# PuzzleBox.net
KiCad netlist of a schematic drawn in EasyEDA
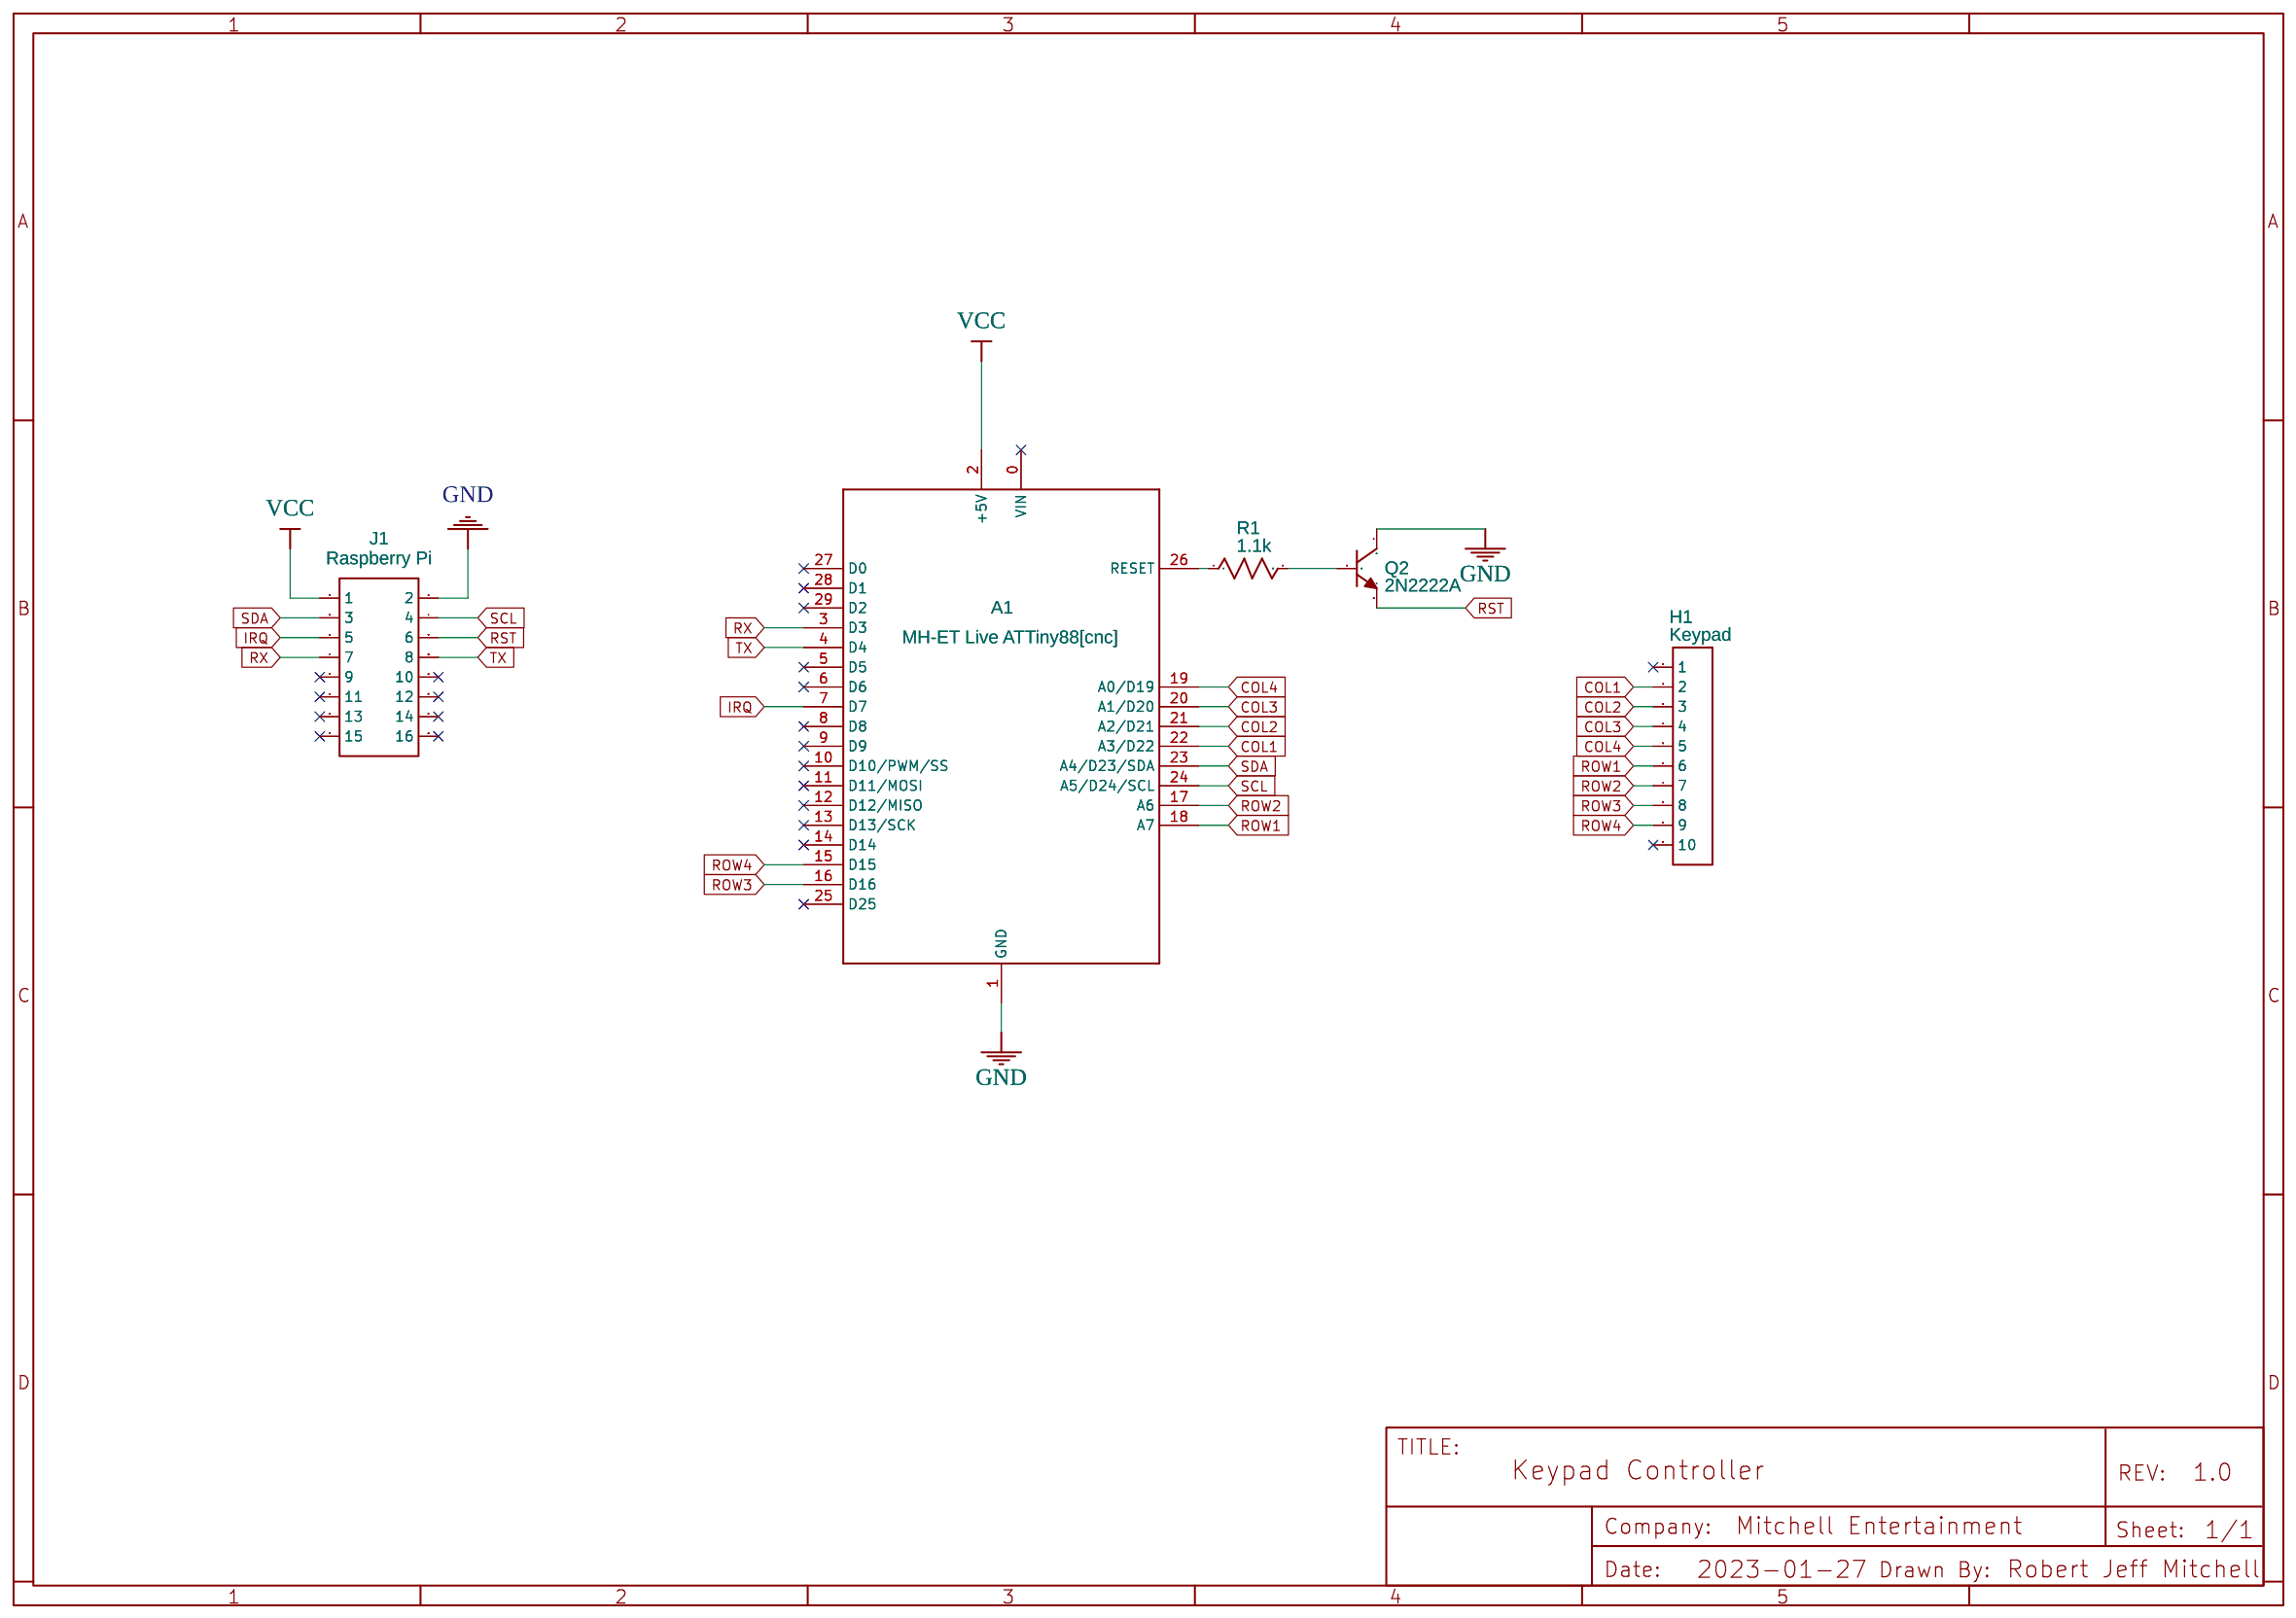
[diagram p0: schematic sheet]

(export (version "E")
  (design (tool "Eeschema 10.0.6"))
  (components
    (comp (ref "A1")
      (value "MH-ET Live ATTiny88[cnc]")
      (libsource (lib "") (part "MH-ET Live ATTiny88[cnc]"))
    )
    (comp (ref "H1")
      (value "Keypad")
      (fields (field (name "BOM_Supplier Part") "C35445"))
      (libsource (lib "") (part "HDR-F-2.54_1x10"))
    )
    (comp (ref "J1")
      (value "Raspberry Pi")
      (fields (field (name "BOM_Supplier Part") "C68234"))
      (libsource (lib "") (part "HDR-M-2.54_2x8"))
    )
    (comp (ref "Q2")
      (value "2N2222A")
      (fields (field (name "BOM_Supplier Part") "C358533"))
      (libsource (lib "") (part "2N2222A"))
    )
    (comp (ref "R1") (value "1.1k") (libsource (lib "") (part "R_AXIAL-0.4_US")))
  )
  (nets
    (net (code "1") (name "COL1") (class "Default")
      (node (ref "A1") (pin "22") (pinfunction "A3/D22_22") (pintype "unspecified"))
      (node (ref "H1") (pin "2") (pinfunction "2_2") (pintype "unspecified"))
    )
    (net (code "2") (name "COL2") (class "Default")
      (node (ref "A1") (pin "21") (pinfunction "A2/D21_21") (pintype "unspecified"))
      (node (ref "H1") (pin "3") (pinfunction "3_3") (pintype "unspecified"))
    )
    (net (code "3") (name "COL3") (class "Default")
      (node (ref "A1") (pin "20") (pinfunction "A1/D20_20") (pintype "unspecified"))
      (node (ref "H1") (pin "4") (pinfunction "4_4") (pintype "unspecified"))
    )
    (net (code "4") (name "COL4") (class "Default")
      (node (ref "A1") (pin "19") (pinfunction "A0/D19_19") (pintype "unspecified"))
      (node (ref "H1") (pin "5") (pinfunction "5_5") (pintype "unspecified"))
    )
    (net (code "5") (name "GND") (class "Default")
      (node (ref "A1") (pin "1") (pinfunction "GND_1") (pintype "passive"))
      (node (ref "J1") (pin "2") (pinfunction "2_2") (pintype "input"))
      (node (ref "Q2") (pin "1") (pinfunction "C_1") (pintype "unspecified"))
    )
    (net (code "6") (name "IRQ") (class "Default")
      (node (ref "A1") (pin "7") (pinfunction "D7_7") (pintype "unspecified"))
      (node (ref "J1") (pin "5") (pinfunction "5_5") (pintype "input"))
    )
    (net (code "7") (name "Net-(A1-RESET)") (class "Default")
      (node (ref "A1") (pin "26") (pinfunction "RESET_26") (pintype "unspecified"))
      (node (ref "R1") (pin "1") (pinfunction "1_1") (pintype "unspecified"))
    )
    (net (code "8") (name "Net-(Q2-B)") (class "Default")
      (node (ref "Q2") (pin "2") (pinfunction "B_2") (pintype "unspecified"))
      (node (ref "R1") (pin "2") (pinfunction "2_2") (pintype "unspecified"))
    )
    (net (code "9") (name "ROW1") (class "Default")
      (node (ref "A1") (pin "18") (pinfunction "A7_18") (pintype "unspecified"))
      (node (ref "H1") (pin "6") (pinfunction "6_6") (pintype "unspecified"))
    )
    (net (code "10") (name "ROW2") (class "Default")
      (node (ref "A1") (pin "17") (pinfunction "A6_17") (pintype "unspecified"))
      (node (ref "H1") (pin "7") (pinfunction "7_7") (pintype "unspecified"))
    )
    (net (code "11") (name "ROW3") (class "Default")
      (node (ref "A1") (pin "16") (pinfunction "D16_16") (pintype "unspecified"))
      (node (ref "H1") (pin "8") (pinfunction "8_8") (pintype "unspecified"))
    )
    (net (code "12") (name "ROW4") (class "Default")
      (node (ref "A1") (pin "15") (pinfunction "D15_15") (pintype "unspecified"))
      (node (ref "H1") (pin "9") (pinfunction "9_9") (pintype "unspecified"))
    )
    (net (code "13") (name "RST") (class "Default")
      (node (ref "J1") (pin "6") (pinfunction "6_6") (pintype "input"))
      (node (ref "Q2") (pin "3") (pinfunction "E_3") (pintype "unspecified"))
    )
    (net (code "14") (name "RX") (class "Default")
      (node (ref "A1") (pin "3") (pinfunction "D3_3") (pintype "unspecified"))
      (node (ref "J1") (pin "7") (pinfunction "7_7") (pintype "input"))
    )
    (net (code "15") (name "SCL") (class "Default")
      (node (ref "A1") (pin "24") (pinfunction "A5/D24/SCL_24") (pintype "unspecified"))
      (node (ref "J1") (pin "4") (pinfunction "4_4") (pintype "input"))
    )
    (net (code "16") (name "SDA") (class "Default")
      (node (ref "A1") (pin "23") (pinfunction "A4/D23/SDA_23") (pintype "unspecified"))
      (node (ref "J1") (pin "3") (pinfunction "3_3") (pintype "input"))
    )
    (net (code "17") (name "TX") (class "Default")
      (node (ref "A1") (pin "4") (pinfunction "D4_4") (pintype "unspecified"))
      (node (ref "J1") (pin "8") (pinfunction "8_8") (pintype "input"))
    )
    (net (code "18") (name "VCC") (class "Default")
      (node (ref "A1") (pin "2") (pinfunction "+5V_2") (pintype "passive"))
      (node (ref "J1") (pin "1") (pinfunction "1_1") (pintype "input"))
    )
    (net (code "19") (name "unconnected-(A1-D0-Pad27)") (class "Default")
      (node (ref "A1") (pin "27") (pinfunction "D0_27") (pintype "unspecified+no_connect"))
    )
    (net (code "20") (name "unconnected-(A1-D1-Pad28)") (class "Default")
      (node (ref "A1") (pin "28") (pinfunction "D1_28") (pintype "unspecified+no_connect"))
    )
    (net (code "21") (name "unconnected-(A1-D2-Pad29)") (class "Default")
      (node (ref "A1") (pin "29") (pinfunction "D2_29") (pintype "unspecified+no_connect"))
    )
    (net (code "22") (name "unconnected-(A1-D5-Pad5)") (class "Default")
      (node (ref "A1") (pin "5") (pinfunction "D5_5") (pintype "unspecified+no_connect"))
    )
    (net (code "23") (name "unconnected-(A1-D6-Pad6)") (class "Default")
      (node (ref "A1") (pin "6") (pinfunction "D6_6") (pintype "unspecified+no_connect"))
    )
    (net (code "24") (name "unconnected-(A1-D8-Pad8)") (class "Default")
      (node (ref "A1") (pin "8") (pinfunction "D8_8") (pintype "unspecified+no_connect"))
    )
    (net (code "25") (name "unconnected-(A1-D9-Pad9)") (class "Default")
      (node (ref "A1") (pin "9") (pinfunction "D9_9") (pintype "unspecified+no_connect"))
    )
    (net (code "26") (name "unconnected-(A1-D10{slash}PWM{slash}SS-Pad10)") (class "Default")
      (node (ref "A1") (pin "10") (pinfunction "D10/PWM/SS_10") (pintype "unspecified+no_connect"))
    )
    (net (code "27") (name "unconnected-(A1-D11{slash}MOSI-Pad11)") (class "Default")
      (node (ref "A1") (pin "11") (pinfunction "D11/MOSI_11") (pintype "unspecified+no_connect"))
    )
    (net (code "28") (name "unconnected-(A1-D12{slash}MISO-Pad12)") (class "Default")
      (node (ref "A1") (pin "12") (pinfunction "D12/MISO_12") (pintype "unspecified+no_connect"))
    )
    (net (code "29") (name "unconnected-(A1-D13{slash}SCK-Pad13)") (class "Default")
      (node (ref "A1") (pin "13") (pinfunction "D13/SCK_13") (pintype "unspecified+no_connect"))
    )
    (net (code "30") (name "unconnected-(A1-D14-Pad14)") (class "Default")
      (node (ref "A1") (pin "14") (pinfunction "D14_14") (pintype "unspecified+no_connect"))
    )
    (net (code "31") (name "unconnected-(A1-D25-Pad25)") (class "Default")
      (node (ref "A1") (pin "25") (pinfunction "D25_25") (pintype "unspecified+no_connect"))
    )
    (net (code "32") (name "unconnected-(A1-VIN-Pad0)") (class "Default")
      (node (ref "A1") (pin "0") (pinfunction "VIN_0") (pintype "passive+no_connect"))
    )
    (net (code "33") (name "unconnected-(H1-Pad1)") (class "Default")
      (node (ref "H1") (pin "1") (pinfunction "1_1") (pintype "unspecified+no_connect"))
    )
    (net (code "34") (name "unconnected-(H1-Pad10)") (class "Default")
      (node (ref "H1") (pin "10") (pinfunction "10_10") (pintype "unspecified+no_connect"))
    )
    (net (code "35") (name "unconnected-(J1-Pad9)") (class "Default")
      (node (ref "J1") (pin "9") (pinfunction "9_9") (pintype "input+no_connect"))
    )
    (net (code "36") (name "unconnected-(J1-Pad10)") (class "Default")
      (node (ref "J1") (pin "10") (pinfunction "10_10") (pintype "input+no_connect"))
    )
    (net (code "37") (name "unconnected-(J1-Pad11)") (class "Default")
      (node (ref "J1") (pin "11") (pinfunction "11_11") (pintype "input+no_connect"))
    )
    (net (code "38") (name "unconnected-(J1-Pad12)") (class "Default")
      (node (ref "J1") (pin "12") (pinfunction "12_12") (pintype "input+no_connect"))
    )
    (net (code "39") (name "unconnected-(J1-Pad13)") (class "Default")
      (node (ref "J1") (pin "13") (pinfunction "13_13") (pintype "input+no_connect"))
    )
    (net (code "40") (name "unconnected-(J1-Pad14)") (class "Default")
      (node (ref "J1") (pin "14") (pinfunction "14_14") (pintype "input+no_connect"))
    )
    (net (code "41") (name "unconnected-(J1-Pad15)") (class "Default")
      (node (ref "J1") (pin "15") (pinfunction "15_15") (pintype "input+no_connect"))
    )
    (net (code "42") (name "unconnected-(J1-Pad16)") (class "Default")
      (node (ref "J1") (pin "16") (pinfunction "16_16") (pintype "input+no_connect"))
    )
  )
)
